# displayNEU.net
KiCad netlist of a schematic drawn in EAGLE
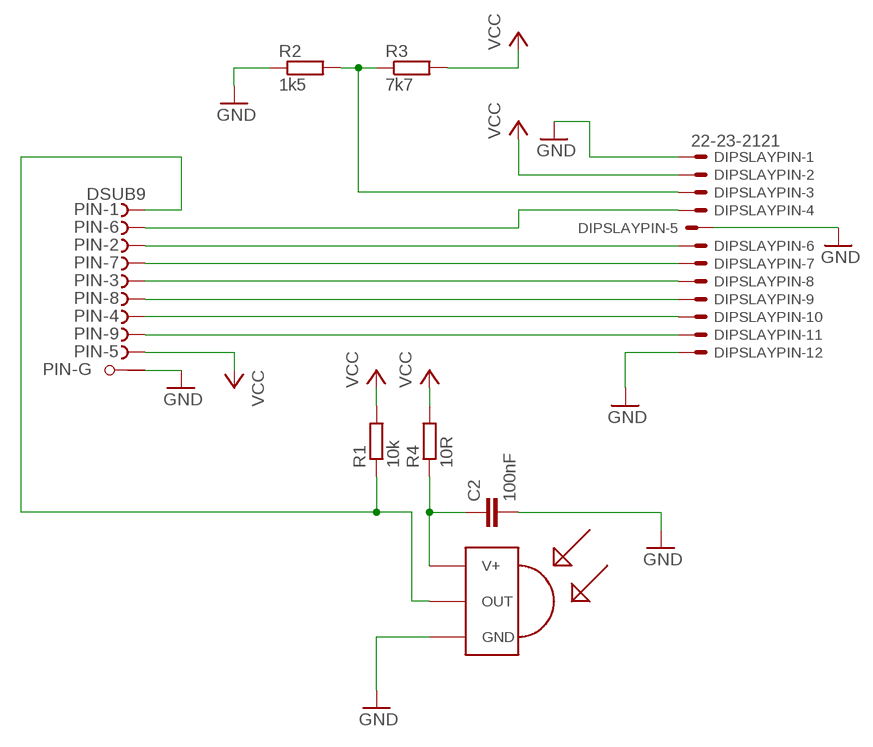
[diagram p0: schematic, sheet 1]

(export (version "E")
  (design (tool "Eeschema 10.0.6"))
  (components
    (comp (ref "C2")
      (value "100nF")
      (footprint "eagle-import:C025-025X050")
      (libsource (lib "eagle-import") (part "C-EU025-025X050"))
    )
    (comp (ref "DIPSLAYPIN")
      (value "22-23-2121")
      (footprint "eagle-import:22-23-2121")
      (fields (field (name "MF") "MOLEX"))
      (libsource (lib "eagle-import") (part "22-23-2121"))
    )
    (comp (ref "PIN")
      (value "DSUB9")
      (footprint "eagle-import:F09HP")
      (libsource (lib "eagle-import") (part "F09HPS"))
    )
    (comp (ref "R1")
      (value "10k")
      (footprint "eagle-import:0207_10")
      (libsource (lib "eagle-import") (part "R-EU_0207/10"))
    )
    (comp (ref "R2")
      (value "1k5")
      (footprint "eagle-import:0207_10")
      (libsource (lib "eagle-import") (part "R-EU_0207/10"))
    )
    (comp (ref "R3")
      (value "7k7")
      (footprint "eagle-import:0207_10")
      (libsource (lib "eagle-import") (part "R-EU_0207/10"))
    )
    (comp (ref "R4")
      (value "10R")
      (footprint "eagle-import:0207_10")
      (libsource (lib "eagle-import") (part "R-EU_0207/10"))
    )
    (comp (ref "U$1")
      (value "TSOP4838")
      (footprint "eagle-import:TSOP18XX")
      (libsource (lib "eagle-import") (part "TSOP4838"))
    )
  )
  (nets
    (net (code "1") (name "GND") (class "Default")
      (node (ref "C2") (pin "2") (pinfunction "2_2") (pintype "passive"))
      (node (ref "DIPSLAYPIN") (pin "1") (pinfunction "S_1") (pintype "passive"))
      (node (ref "DIPSLAYPIN") (pin "12") (pinfunction "S_12") (pintype "passive"))
      (node (ref "DIPSLAYPIN") (pin "5") (pinfunction "S_5") (pintype "passive"))
      (node (ref "PIN") (pin "G1") (pinfunction "G1_G1") (pintype "passive"))
      (node (ref "R2") (pin "1") (pinfunction "1_1") (pintype "passive"))
      (node (ref "U$1") (pin "GND") (pinfunction "GND_GND") (pintype "bidirectional"))
    )
    (net (code "2") (name "Net-(DIPSLAYPINB-S)") (class "Default")
      (node (ref "DIPSLAYPIN") (pin "10") (pinfunction "S_10") (pintype "passive"))
      (node (ref "PIN") (pin "4") (pinfunction "F_4") (pintype "passive"))
    )
    (net (code "3") (name "Net-(DIPSLAYPINC-S)") (class "Default")
      (node (ref "DIPSLAYPIN") (pin "11") (pinfunction "S_11") (pintype "passive"))
      (node (ref "PIN") (pin "9") (pinfunction "F_9") (pintype "passive"))
    )
    (net (code "4") (name "Net-(DIPSLAYPINF-S)") (class "Default")
      (node (ref "DIPSLAYPIN") (pin "3") (pinfunction "S_3") (pintype "passive"))
      (node (ref "R2") (pin "2") (pinfunction "2_2") (pintype "passive"))
      (node (ref "R3") (pin "1") (pinfunction "1_1") (pintype "passive"))
    )
    (net (code "5") (name "Net-(DIPSLAYPING-S)") (class "Default")
      (node (ref "DIPSLAYPIN") (pin "4") (pinfunction "S_4") (pintype "passive"))
      (node (ref "PIN") (pin "6") (pinfunction "F_6") (pintype "passive"))
    )
    (net (code "6") (name "Net-(DIPSLAYPINI-S)") (class "Default")
      (node (ref "DIPSLAYPIN") (pin "6") (pinfunction "S_6") (pintype "passive"))
      (node (ref "PIN") (pin "2") (pinfunction "F_2") (pintype "passive"))
    )
    (net (code "7") (name "Net-(DIPSLAYPINJ-S)") (class "Default")
      (node (ref "DIPSLAYPIN") (pin "7") (pinfunction "S_7") (pintype "passive"))
      (node (ref "PIN") (pin "7") (pinfunction "F_7") (pintype "passive"))
    )
    (net (code "8") (name "Net-(DIPSLAYPINK-S)") (class "Default")
      (node (ref "DIPSLAYPIN") (pin "8") (pinfunction "S_8") (pintype "passive"))
      (node (ref "PIN") (pin "3") (pinfunction "F_3") (pintype "passive"))
    )
    (net (code "9") (name "Net-(DIPSLAYPINL-S)") (class "Default")
      (node (ref "DIPSLAYPIN") (pin "9") (pinfunction "S_9") (pintype "passive"))
      (node (ref "PIN") (pin "8") (pinfunction "F_8") (pintype "passive"))
    )
    (net (code "10") (name "Net-(PINA-F)") (class "Default")
      (node (ref "PIN") (pin "1") (pinfunction "F_1") (pintype "passive"))
      (node (ref "R1") (pin "1") (pinfunction "1_1") (pintype "passive"))
      (node (ref "U$1") (pin "OUT") (pinfunction "OUT_OUT") (pintype "bidirectional"))
    )
    (net (code "11") (name "Net-(U$1-V+)") (class "Default")
      (node (ref "C2") (pin "1") (pinfunction "1_1") (pintype "passive"))
      (node (ref "R4") (pin "1") (pinfunction "1_1") (pintype "passive"))
      (node (ref "U$1") (pin "VCC") (pinfunction "V+_VCC") (pintype "bidirectional"))
    )
    (net (code "12") (name "VCC") (class "Default")
      (node (ref "DIPSLAYPIN") (pin "2") (pinfunction "S_2") (pintype "passive"))
      (node (ref "PIN") (pin "5") (pinfunction "F_5") (pintype "passive"))
      (node (ref "R1") (pin "2") (pinfunction "2_2") (pintype "passive"))
      (node (ref "R3") (pin "2") (pinfunction "2_2") (pintype "passive"))
      (node (ref "R4") (pin "2") (pinfunction "2_2") (pintype "passive"))
    )
    (net (code "13") (name "unconnected-(PIN-PadG2)") (class "Default")
      (node (ref "PIN") (pin "G2") (pinfunction "G2_G2") (pintype "passive"))
    )
  )
)
